# schematicDiagramTransmitterBoard.net
KiCad netlist of a schematic drawn in EAGLE
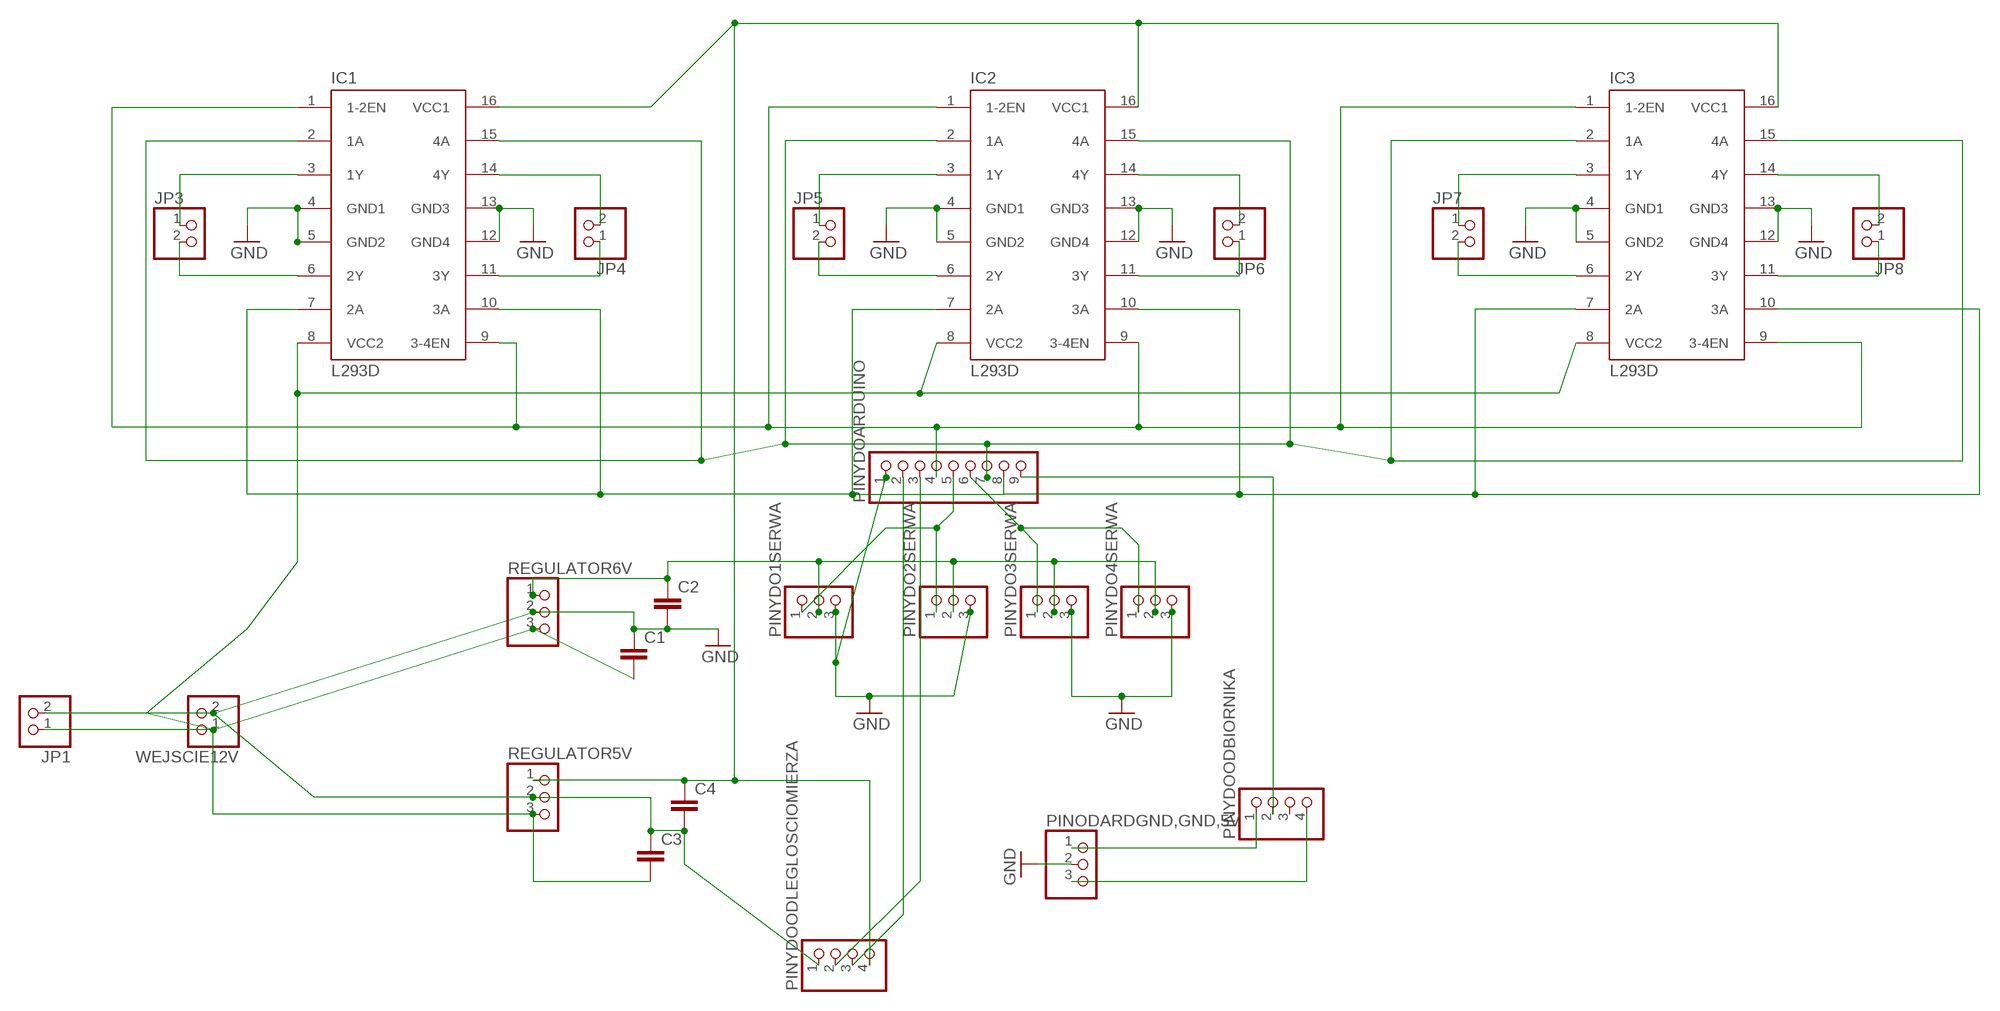
[diagram p0: schematic, sheet 1]

(export (version "E")
  (design (tool "Eeschema 10.0.6"))
  (components
    (comp (ref "C1")
      (value "C2,5-3")
      (footprint "eagle-import:C2.5-3")
      (libsource (lib "eagle-import") (part "C2,5-3"))
    )
    (comp (ref "C2")
      (value "C2,5-3")
      (footprint "eagle-import:C2.5-3")
      (libsource (lib "eagle-import") (part "C2,5-3"))
    )
    (comp (ref "C3")
      (value "C2,5-3")
      (footprint "eagle-import:C2.5-3")
      (libsource (lib "eagle-import") (part "C2,5-3"))
    )
    (comp (ref "C4")
      (value "C2,5-3")
      (footprint "eagle-import:C2.5-3")
      (libsource (lib "eagle-import") (part "C2,5-3"))
    )
    (comp (ref "IC1")
      (value "L293D")
      (footprint "eagle-import:DIL16")
      (libsource (lib "eagle-import") (part "L293D"))
    )
    (comp (ref "IC2")
      (value "L293D")
      (footprint "eagle-import:DIL16")
      (libsource (lib "eagle-import") (part "L293D"))
    )
    (comp (ref "IC3")
      (value "L293D")
      (footprint "eagle-import:DIL16")
      (libsource (lib "eagle-import") (part "L293D"))
    )
    (comp (ref "JP1")
      (value "PINHD-1X2")
      (footprint "eagle-import:1X02")
      (libsource (lib "eagle-import") (part "PINHD-1X2"))
    )
    (comp (ref "JP3")
      (value "PINHD-1X2")
      (footprint "eagle-import:1X02")
      (libsource (lib "eagle-import") (part "PINHD-1X2"))
    )
    (comp (ref "JP4")
      (value "PINHD-1X2")
      (footprint "eagle-import:1X02")
      (libsource (lib "eagle-import") (part "PINHD-1X2"))
    )
    (comp (ref "JP5")
      (value "PINHD-1X2")
      (footprint "eagle-import:1X02")
      (libsource (lib "eagle-import") (part "PINHD-1X2"))
    )
    (comp (ref "JP6")
      (value "PINHD-1X2")
      (footprint "eagle-import:1X02")
      (libsource (lib "eagle-import") (part "PINHD-1X2"))
    )
    (comp (ref "JP7")
      (value "PINHD-1X2")
      (footprint "eagle-import:1X02")
      (libsource (lib "eagle-import") (part "PINHD-1X2"))
    )
    (comp (ref "JP8")
      (value "PINHD-1X2")
      (footprint "eagle-import:1X02")
      (libsource (lib "eagle-import") (part "PINHD-1X2"))
    )
    (comp (ref "PINODARDGND,GND,5V")
      (value "PINHD-1X3")
      (footprint "eagle-import:1X03")
      (libsource (lib "eagle-import") (part "PINHD-1X3"))
    )
    (comp (ref "PINYDO1SERWA")
      (value "PINHD-1X3")
      (footprint "eagle-import:1X03")
      (libsource (lib "eagle-import") (part "PINHD-1X3"))
    )
    (comp (ref "PINYDO2SERWA")
      (value "PINHD-1X3")
      (footprint "eagle-import:1X03")
      (libsource (lib "eagle-import") (part "PINHD-1X3"))
    )
    (comp (ref "PINYDO3SERWA")
      (value "PINHD-1X3")
      (footprint "eagle-import:1X03")
      (libsource (lib "eagle-import") (part "PINHD-1X3"))
    )
    (comp (ref "PINYDO4SERWA")
      (value "PINHD-1X3")
      (footprint "eagle-import:1X03")
      (libsource (lib "eagle-import") (part "PINHD-1X3"))
    )
    (comp (ref "PINYDOARDUINO")
      (value "PINHD-1X9")
      (footprint "eagle-import:1X09")
      (libsource (lib "eagle-import") (part "PINHD-1X9"))
    )
    (comp (ref "PINYDOODBIORNIKA")
      (value "PINHD-1X4")
      (footprint "eagle-import:1X04")
      (libsource (lib "eagle-import") (part "PINHD-1X4"))
    )
    (comp (ref "PINYDOODLEGLOSCIOMIERZA")
      (value "PINHD-1X4")
      (footprint "eagle-import:1X04")
      (libsource (lib "eagle-import") (part "PINHD-1X4"))
    )
    (comp (ref "REGULATOR5V")
      (value "PINHD-1X3")
      (footprint "eagle-import:1X03")
      (libsource (lib "eagle-import") (part "PINHD-1X3"))
    )
    (comp (ref "REGULATOR6V")
      (value "PINHD-1X3")
      (footprint "eagle-import:1X03")
      (libsource (lib "eagle-import") (part "PINHD-1X3"))
    )
    (comp (ref "WEJSCIE12V")
      (value "PINHD-1X2")
      (footprint "eagle-import:1X02")
      (libsource (lib "eagle-import") (part "PINHD-1X2"))
    )
  )
  (nets
    (net (code "1") (name "GND") (class "Default")
      (node (ref "C1") (pin "1") (pinfunction "1_1") (pintype "passive"))
      (node (ref "C2") (pin "2") (pinfunction "2_2") (pintype "passive"))
      (node (ref "C3") (pin "1") (pinfunction "1_1") (pintype "passive"))
      (node (ref "C4") (pin "2") (pinfunction "2_2") (pintype "passive"))
      (node (ref "IC1") (pin "12") (pinfunction "GND4_12") (pintype "power_in"))
      (node (ref "IC1") (pin "13") (pinfunction "GND3_13") (pintype "power_in"))
      (node (ref "IC1") (pin "4") (pinfunction "GND1_4") (pintype "power_in"))
      (node (ref "IC1") (pin "5") (pinfunction "GND2_5") (pintype "power_in"))
      (node (ref "IC2") (pin "12") (pinfunction "GND4_12") (pintype "power_in"))
      (node (ref "IC2") (pin "13") (pinfunction "GND3_13") (pintype "power_in"))
      (node (ref "IC2") (pin "4") (pinfunction "GND1_4") (pintype "power_in"))
      (node (ref "IC2") (pin "5") (pinfunction "GND2_5") (pintype "power_in"))
      (node (ref "IC3") (pin "12") (pinfunction "GND4_12") (pintype "power_in"))
      (node (ref "IC3") (pin "13") (pinfunction "GND3_13") (pintype "power_in"))
      (node (ref "IC3") (pin "4") (pinfunction "GND1_4") (pintype "power_in"))
      (node (ref "IC3") (pin "5") (pinfunction "GND2_5") (pintype "power_in"))
      (node (ref "JP1") (pin "2") (pinfunction "2_2") (pintype "passive"))
      (node (ref "PINODARDGND,GND,5V") (pin "2") (pinfunction "2_2") (pintype "passive"))
      (node (ref "PINYDO1SERWA") (pin "3") (pinfunction "3_3") (pintype "passive"))
      (node (ref "PINYDO2SERWA") (pin "3") (pinfunction "3_3") (pintype "passive"))
      (node (ref "PINYDO3SERWA") (pin "3") (pinfunction "3_3") (pintype "passive"))
      (node (ref "PINYDO4SERWA") (pin "3") (pinfunction "3_3") (pintype "passive"))
      (node (ref "PINYDOARDUINO") (pin "1") (pinfunction "1_1") (pintype "passive"))
      (node (ref "PINYDOODLEGLOSCIOMIERZA") (pin "1") (pinfunction "1_1") (pintype "passive"))
      (node (ref "REGULATOR5V") (pin "2") (pinfunction "2_2") (pintype "passive"))
      (node (ref "REGULATOR6V") (pin "2") (pinfunction "2_2") (pintype "passive"))
      (node (ref "WEJSCIE12V") (pin "2") (pinfunction "2_2") (pintype "passive"))
    )
    (net (code "2") (name "Net-(C2-Pad1)") (class "Default")
      (node (ref "C2") (pin "1") (pinfunction "1_1") (pintype "passive"))
      (node (ref "PINYDO1SERWA") (pin "2") (pinfunction "2_2") (pintype "passive"))
      (node (ref "PINYDO2SERWA") (pin "2") (pinfunction "2_2") (pintype "passive"))
      (node (ref "PINYDO3SERWA") (pin "2") (pinfunction "2_2") (pintype "passive"))
      (node (ref "PINYDO4SERWA") (pin "2") (pinfunction "2_2") (pintype "passive"))
      (node (ref "REGULATOR6V") (pin "1") (pinfunction "1_1") (pintype "passive"))
    )
    (net (code "3") (name "Net-(IC1-1-2EN)") (class "Default")
      (node (ref "IC1") (pin "1") (pinfunction "1-2EN_1") (pintype "input"))
      (node (ref "IC1") (pin "9") (pinfunction "3-4EN_9") (pintype "input"))
      (node (ref "IC2") (pin "1") (pinfunction "1-2EN_1") (pintype "input"))
      (node (ref "IC2") (pin "9") (pinfunction "3-4EN_9") (pintype "input"))
      (node (ref "IC3") (pin "1") (pinfunction "1-2EN_1") (pintype "input"))
      (node (ref "IC3") (pin "9") (pinfunction "3-4EN_9") (pintype "input"))
      (node (ref "PINYDOARDUINO") (pin "4") (pinfunction "4_4") (pintype "passive"))
    )
    (net (code "4") (name "Net-(IC1-1A)") (class "Default")
      (node (ref "IC1") (pin "15") (pinfunction "4A_15") (pintype "input"))
      (node (ref "IC1") (pin "2") (pinfunction "1A_2") (pintype "input"))
      (node (ref "IC2") (pin "15") (pinfunction "4A_15") (pintype "input"))
      (node (ref "IC2") (pin "2") (pinfunction "1A_2") (pintype "input"))
      (node (ref "IC3") (pin "15") (pinfunction "4A_15") (pintype "input"))
      (node (ref "IC3") (pin "2") (pinfunction "1A_2") (pintype "input"))
      (node (ref "PINYDOARDUINO") (pin "7") (pinfunction "7_7") (pintype "passive"))
    )
    (net (code "5") (name "Net-(IC1-1Y)") (class "Default")
      (node (ref "IC1") (pin "3") (pinfunction "1Y_3") (pintype "output"))
      (node (ref "JP3") (pin "1") (pinfunction "1_1") (pintype "passive"))
    )
    (net (code "6") (name "Net-(IC1-2A)") (class "Default")
      (node (ref "IC1") (pin "10") (pinfunction "3A_10") (pintype "input"))
      (node (ref "IC1") (pin "7") (pinfunction "2A_7") (pintype "input"))
      (node (ref "IC2") (pin "10") (pinfunction "3A_10") (pintype "input"))
      (node (ref "IC2") (pin "7") (pinfunction "2A_7") (pintype "input"))
      (node (ref "IC3") (pin "10") (pinfunction "3A_10") (pintype "input"))
      (node (ref "IC3") (pin "7") (pinfunction "2A_7") (pintype "input"))
      (node (ref "PINYDOARDUINO") (pin "8") (pinfunction "8_8") (pintype "passive"))
    )
    (net (code "7") (name "Net-(IC1-2Y)") (class "Default")
      (node (ref "IC1") (pin "6") (pinfunction "2Y_6") (pintype "output"))
      (node (ref "JP3") (pin "2") (pinfunction "2_2") (pintype "passive"))
    )
    (net (code "8") (name "Net-(IC1-3Y)") (class "Default")
      (node (ref "IC1") (pin "11") (pinfunction "3Y_11") (pintype "output"))
      (node (ref "JP4") (pin "1") (pinfunction "1_1") (pintype "passive"))
    )
    (net (code "9") (name "Net-(IC1-4Y)") (class "Default")
      (node (ref "IC1") (pin "14") (pinfunction "4Y_14") (pintype "output"))
      (node (ref "JP4") (pin "2") (pinfunction "2_2") (pintype "passive"))
    )
    (net (code "10") (name "Net-(IC1-VCC1)") (class "Default")
      (node (ref "C4") (pin "1") (pinfunction "1_1") (pintype "passive"))
      (node (ref "IC1") (pin "16") (pinfunction "VCC1_16") (pintype "power_in"))
      (node (ref "IC2") (pin "16") (pinfunction "VCC1_16") (pintype "power_in"))
      (node (ref "IC3") (pin "16") (pinfunction "VCC1_16") (pintype "power_in"))
      (node (ref "PINYDOODLEGLOSCIOMIERZA") (pin "4") (pinfunction "4_4") (pintype "passive"))
      (node (ref "REGULATOR5V") (pin "1") (pinfunction "1_1") (pintype "passive"))
    )
    (net (code "11") (name "Net-(IC1-VCC2)") (class "Default")
      (node (ref "C1") (pin "2") (pinfunction "2_2") (pintype "passive"))
      (node (ref "C3") (pin "2") (pinfunction "2_2") (pintype "passive"))
      (node (ref "IC1") (pin "8") (pinfunction "VCC2_8") (pintype "power_in"))
      (node (ref "IC2") (pin "8") (pinfunction "VCC2_8") (pintype "power_in"))
      (node (ref "IC3") (pin "8") (pinfunction "VCC2_8") (pintype "power_in"))
      (node (ref "JP1") (pin "1") (pinfunction "1_1") (pintype "passive"))
      (node (ref "REGULATOR5V") (pin "3") (pinfunction "3_3") (pintype "passive"))
      (node (ref "REGULATOR6V") (pin "3") (pinfunction "3_3") (pintype "passive"))
      (node (ref "WEJSCIE12V") (pin "1") (pinfunction "1_1") (pintype "passive"))
    )
    (net (code "12") (name "Net-(IC2-1Y)") (class "Default")
      (node (ref "IC2") (pin "3") (pinfunction "1Y_3") (pintype "output"))
      (node (ref "JP5") (pin "1") (pinfunction "1_1") (pintype "passive"))
    )
    (net (code "13") (name "Net-(IC2-2Y)") (class "Default")
      (node (ref "IC2") (pin "6") (pinfunction "2Y_6") (pintype "output"))
      (node (ref "JP5") (pin "2") (pinfunction "2_2") (pintype "passive"))
    )
    (net (code "14") (name "Net-(IC2-3Y)") (class "Default")
      (node (ref "IC2") (pin "11") (pinfunction "3Y_11") (pintype "output"))
      (node (ref "JP6") (pin "1") (pinfunction "1_1") (pintype "passive"))
    )
    (net (code "15") (name "Net-(IC2-4Y)") (class "Default")
      (node (ref "IC2") (pin "14") (pinfunction "4Y_14") (pintype "output"))
      (node (ref "JP6") (pin "2") (pinfunction "2_2") (pintype "passive"))
    )
    (net (code "16") (name "Net-(IC3-1Y)") (class "Default")
      (node (ref "IC3") (pin "3") (pinfunction "1Y_3") (pintype "output"))
      (node (ref "JP7") (pin "1") (pinfunction "1_1") (pintype "passive"))
    )
    (net (code "17") (name "Net-(IC3-2Y)") (class "Default")
      (node (ref "IC3") (pin "6") (pinfunction "2Y_6") (pintype "output"))
      (node (ref "JP7") (pin "2") (pinfunction "2_2") (pintype "passive"))
    )
    (net (code "18") (name "Net-(IC3-3Y)") (class "Default")
      (node (ref "IC3") (pin "11") (pinfunction "3Y_11") (pintype "output"))
      (node (ref "JP8") (pin "1") (pinfunction "1_1") (pintype "passive"))
    )
    (net (code "19") (name "Net-(IC3-4Y)") (class "Default")
      (node (ref "IC3") (pin "14") (pinfunction "4Y_14") (pintype "output"))
      (node (ref "JP8") (pin "2") (pinfunction "2_2") (pintype "passive"))
    )
    (net (code "20") (name "Net-(PINODARDGND,GND,5V-Pad1)") (class "Default")
      (node (ref "PINODARDGND,GND,5V") (pin "1") (pinfunction "1_1") (pintype "passive"))
      (node (ref "PINYDOODBIORNIKA") (pin "1") (pinfunction "1_1") (pintype "passive"))
    )
    (net (code "21") (name "Net-(PINODARDGND,GND,5V-Pad3)") (class "Default")
      (node (ref "PINODARDGND,GND,5V") (pin "3") (pinfunction "3_3") (pintype "passive"))
      (node (ref "PINYDOODBIORNIKA") (pin "4") (pinfunction "4_4") (pintype "passive"))
    )
    (net (code "22") (name "Net-(PINYDO1SERWA-Pad1)") (class "Default")
      (node (ref "PINYDO1SERWA") (pin "1") (pinfunction "1_1") (pintype "passive"))
      (node (ref "PINYDO2SERWA") (pin "1") (pinfunction "1_1") (pintype "passive"))
      (node (ref "PINYDOARDUINO") (pin "5") (pinfunction "5_5") (pintype "passive"))
    )
    (net (code "23") (name "Net-(PINYDO3SERWA-Pad1)") (class "Default")
      (node (ref "PINYDO3SERWA") (pin "1") (pinfunction "1_1") (pintype "passive"))
      (node (ref "PINYDO4SERWA") (pin "1") (pinfunction "1_1") (pintype "passive"))
      (node (ref "PINYDOARDUINO") (pin "6") (pinfunction "6_6") (pintype "passive"))
    )
    (net (code "24") (name "Net-(PINYDOARDUINO-Pad2)") (class "Default")
      (node (ref "PINYDOARDUINO") (pin "2") (pinfunction "2_2") (pintype "passive"))
      (node (ref "PINYDOODLEGLOSCIOMIERZA") (pin "3") (pinfunction "3_3") (pintype "passive"))
    )
    (net (code "25") (name "Net-(PINYDOARDUINO-Pad3)") (class "Default")
      (node (ref "PINYDOARDUINO") (pin "3") (pinfunction "3_3") (pintype "passive"))
      (node (ref "PINYDOODLEGLOSCIOMIERZA") (pin "2") (pinfunction "2_2") (pintype "passive"))
    )
    (net (code "26") (name "Net-(PINYDOARDUINO-Pad9)") (class "Default")
      (node (ref "PINYDOARDUINO") (pin "9") (pinfunction "9_9") (pintype "passive"))
      (node (ref "PINYDOODBIORNIKA") (pin "2") (pinfunction "2_2") (pintype "passive"))
    )
    (net (code "27") (name "unconnected-(PINYDOODBIORNIKA-Pad3)") (class "Default")
      (node (ref "PINYDOODBIORNIKA") (pin "3") (pinfunction "3_3") (pintype "passive"))
    )
  )
)
